# 5VAC-DCReg.net
KiCad netlist of a schematic drawn in EAGLE
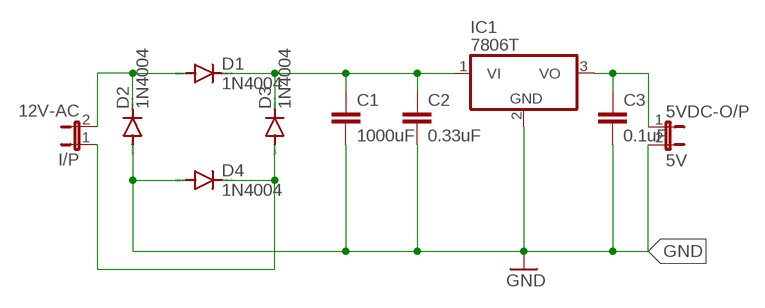
[diagram p0: schematic, sheet 1]

(export (version "E")
  (design (tool "Eeschema 10.0.6"))
  (components
    (comp (ref "5VDC-O/P")
      (value "5V")
      (footprint "eagle-import:JP1")
      (libsource (lib "eagle-import") (part "JP1E"))
    )
    (comp (ref "C1")
      (value "1000uF")
      (footprint "eagle-import:C2.5-3")
      (libsource (lib "eagle-import") (part "C2,5-3"))
    )
    (comp (ref "C2")
      (value "0.33uF")
      (footprint "eagle-import:C2.5-3")
      (libsource (lib "eagle-import") (part "C2,5-3"))
    )
    (comp (ref "C3")
      (value "0.1uF")
      (footprint "eagle-import:C2.5-3")
      (libsource (lib "eagle-import") (part "C2,5-3"))
    )
    (comp (ref "D1")
      (value "1N4004")
      (footprint "eagle-import:DO41-10")
      (libsource (lib "eagle-import") (part "1N4004"))
    )
    (comp (ref "D2")
      (value "1N4004")
      (footprint "eagle-import:DO41-10")
      (libsource (lib "eagle-import") (part "1N4004"))
    )
    (comp (ref "D3")
      (value "1N4004")
      (footprint "eagle-import:DO41-10")
      (libsource (lib "eagle-import") (part "1N4004"))
    )
    (comp (ref "D4")
      (value "1N4004")
      (footprint "eagle-import:DO41-10")
      (libsource (lib "eagle-import") (part "1N4004"))
    )
    (comp (ref "I/P")
      (value "12V-AC")
      (footprint "eagle-import:JP1")
      (libsource (lib "eagle-import") (part "JP1E"))
    )
    (comp (ref "IC1")
      (value "7806T")
      (footprint "eagle-import:TO220H")
      (libsource (lib "eagle-import") (part "78T06"))
    )
  )
  (nets
    (net (code "1") (name "GND") (class "Default")
      (node (ref "5VDC-O/P") (pin "2") (pinfunction "2_2") (pintype "passive"))
      (node (ref "C1") (pin "2") (pinfunction "2_2") (pintype "passive"))
      (node (ref "C2") (pin "2") (pinfunction "2_2") (pintype "passive"))
      (node (ref "C3") (pin "2") (pinfunction "2_2") (pintype "passive"))
      (node (ref "D2") (pin "A") (pinfunction "A_A") (pintype "passive"))
      (node (ref "D4") (pin "A") (pinfunction "A_A") (pintype "passive"))
      (node (ref "IC1") (pin "2") (pinfunction "GND_2") (pintype "passive"))
    )
    (net (code "2") (name "Net-(D1-PadA)") (class "Default")
      (node (ref "D1") (pin "A") (pinfunction "A_A") (pintype "passive"))
      (node (ref "D2") (pin "C") (pinfunction "C_C") (pintype "passive"))
      (node (ref "I/P") (pin "2") (pinfunction "2_2") (pintype "passive"))
    )
    (net (code "3") (name "Net-(D3-PadA)") (class "Default")
      (node (ref "D3") (pin "A") (pinfunction "A_A") (pintype "passive"))
      (node (ref "D4") (pin "C") (pinfunction "C_C") (pintype "passive"))
      (node (ref "I/P") (pin "1") (pinfunction "1_1") (pintype "passive"))
    )
    (net (code "4") (name "Net-(IC1-VI)") (class "Default")
      (node (ref "C1") (pin "1") (pinfunction "1_1") (pintype "passive"))
      (node (ref "C2") (pin "1") (pinfunction "1_1") (pintype "passive"))
      (node (ref "D1") (pin "C") (pinfunction "C_C") (pintype "passive"))
      (node (ref "D3") (pin "C") (pinfunction "C_C") (pintype "passive"))
      (node (ref "IC1") (pin "1") (pinfunction "VI_1") (pintype "input"))
    )
    (net (code "5") (name "Net-(IC1-VO)") (class "Default")
      (node (ref "5VDC-O/P") (pin "1") (pinfunction "1_1") (pintype "passive"))
      (node (ref "C3") (pin "1") (pinfunction "1_1") (pintype "passive"))
      (node (ref "IC1") (pin "3") (pinfunction "VO_3") (pintype "passive"))
    )
  )
)
